# DOAN2.net
KiCad netlist of a schematic drawn in Altium Designer
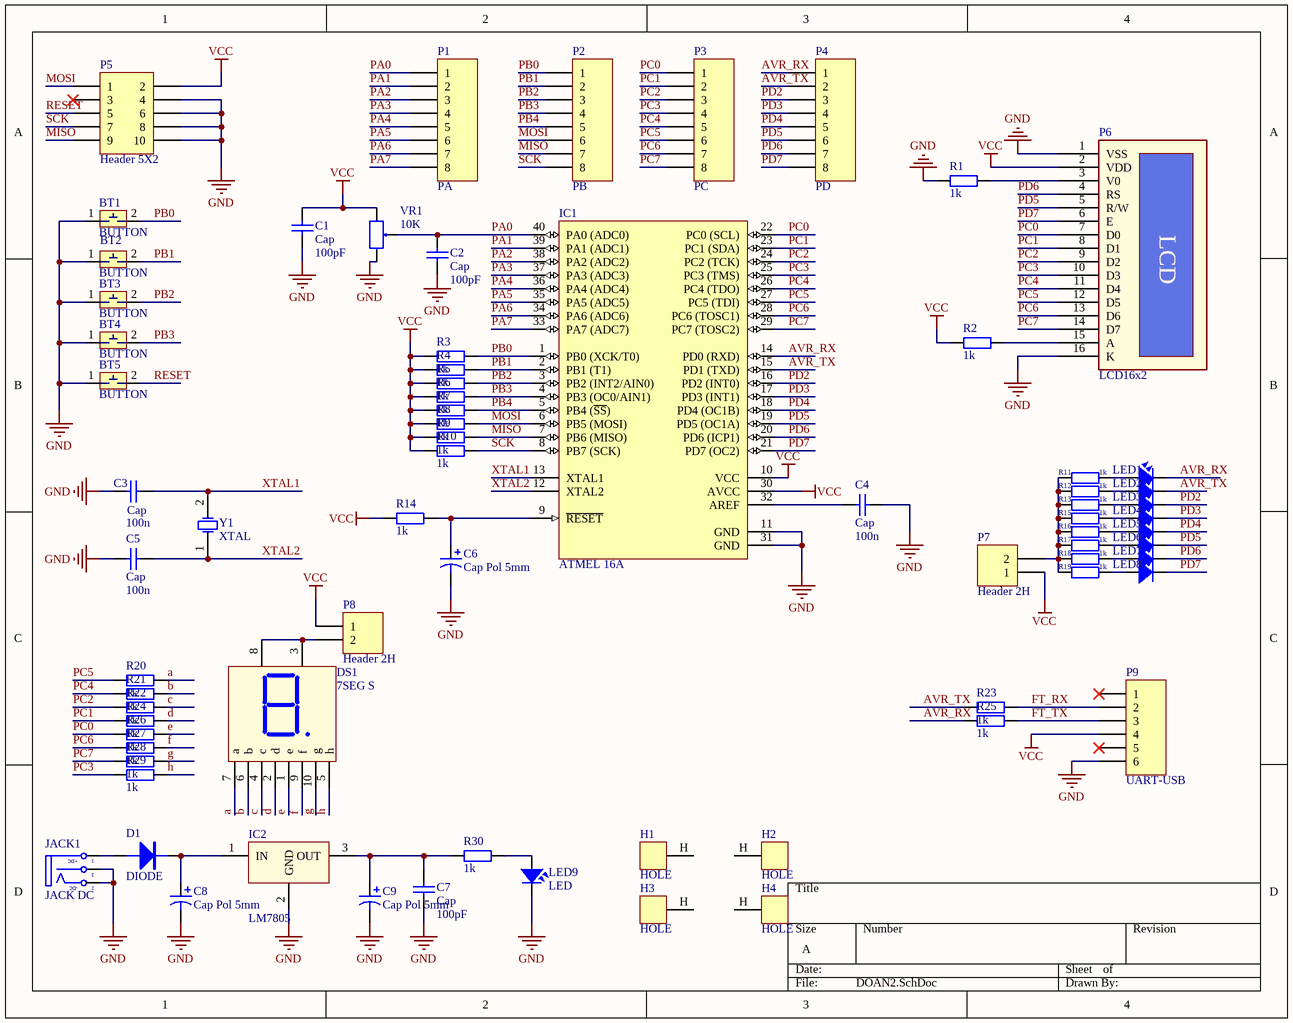
[diagram p0: DOAN2.SchDoc]

(export (version "E")
  (design (tool "Eeschema 10.0.6"))
  (components
    (comp (ref "BT1")
      (value "BUTTON")
      (footprint "BUTTON 4 PIN")
      (libsource (lib "ThinhNguyenLib") (part "BUTTON"))
    )
    (comp (ref "BT2")
      (value "BUTTON")
      (footprint "BUTTON 4 PIN")
      (libsource (lib "ThinhNguyenLib") (part "BUTTON"))
    )
    (comp (ref "BT3")
      (value "BUTTON")
      (footprint "BUTTON 4 PIN")
      (libsource (lib "ThinhNguyenLib") (part "BUTTON"))
    )
    (comp (ref "BT4")
      (value "BUTTON")
      (footprint "BUTTON 4 PIN")
      (libsource (lib "ThinhNguyenLib") (part "BUTTON"))
    )
    (comp (ref "BT5")
      (value "BUTTON")
      (footprint "BUTTON 4 PIN")
      (libsource (lib "ThinhNguyenLib") (part "BUTTON"))
    )
    (comp (ref "C1")
      (value "Cap")
      (footprint "CAP 10x DIP")
      (description "Capacitor")
      (fields (field (name "ALTIUM_VALUE") "100pF") (field (name "PUBLISHER") "Altium Limited"))
      (libsource (lib "Miscellaneous Devices") (part "Cap"))
    )
    (comp (ref "C2")
      (value "Cap")
      (footprint "CAP 10x DIP")
      (description "Capacitor")
      (fields (field (name "ALTIUM_VALUE") "100pF") (field (name "PUBLISHER") "Altium Limited"))
      (libsource (lib "Miscellaneous Devices") (part "Cap"))
    )
    (comp (ref "C3")
      (value "Cap")
      (footprint "CAP 10x DIP")
      (description "Capacitor")
      (fields (field (name "ALTIUM_VALUE") "100n") (field (name "PUBLISHER") "Altium Limited"))
      (libsource (lib "Miscellaneous Devices") (part "Cap"))
    )
    (comp (ref "C4")
      (value "Cap")
      (footprint "CAP 10x DIP")
      (description "Capacitor")
      (fields (field (name "ALTIUM_VALUE") "100n") (field (name "PUBLISHER") "Altium Limited"))
      (libsource (lib "Miscellaneous Devices") (part "Cap"))
    )
    (comp (ref "C5")
      (value "Cap")
      (footprint "CAP 10x DIP")
      (description "Capacitor")
      (fields (field (name "ALTIUM_VALUE") "100n") (field (name "PUBLISHER") "Altium Limited"))
      (libsource (lib "Miscellaneous Devices") (part "Cap"))
    )
    (comp (ref "C6")
      (value "Cap Pol 5mm")
      (footprint "C5mm")
      (description "Polarized Capacitor (Axial)")
      (fields (field (name "PUBLISHER") "Altium Limited"))
      (libsource (lib "My Library") (part "Cap Pol 5mm"))
    )
    (comp (ref "C7")
      (value "Cap")
      (footprint "CAP 10x DIP")
      (description "Capacitor")
      (fields (field (name "ALTIUM_VALUE") "100pF") (field (name "PUBLISHER") "Altium Limited"))
      (libsource (lib "Miscellaneous Devices") (part "Cap"))
    )
    (comp (ref "C8")
      (value "Cap Pol 5mm")
      (footprint "CAP_D10")
      (description "Polarized Capacitor (Axial)")
      (fields (field (name "PUBLISHER") "Altium Limited"))
      (libsource (lib "My Library") (part "Cap Pol 5mm"))
    )
    (comp (ref "C9")
      (value "Cap Pol 5mm")
      (footprint "CAP_D18")
      (description "Polarized Capacitor (Axial)")
      (fields (field (name "PUBLISHER") "Altium Limited"))
      (libsource (lib "My Library") (part "Cap Pol 5mm"))
    )
    (comp (ref "D1")
      (value "DIODE")
      (footprint "DIODE DIP")
      (libsource (lib "ThinhNguyenLib") (part "DIODE"))
    )
    (comp (ref "DS1")
      (value "7SEG S")
      (footprint "7SEGS")
      (description "Single 7 Seg Dipslay")
      (libsource (lib "My Library") (part "LED7S"))
    )
    (comp (ref "H1") (value "HOLE") (footprint "HOLE") (libsource (lib "") (part "HOLE_1")))
    (comp (ref "H2") (value "HOLE") (footprint "HOLE") (libsource (lib "ThinhNguyenLib") (part "HOLE")))
    (comp (ref "H3") (value "HOLE") (footprint "HOLE") (libsource (lib "") (part "HOLE_1")))
    (comp (ref "H4") (value "HOLE") (footprint "HOLE") (libsource (lib "ThinhNguyenLib") (part "HOLE")))
    (comp (ref "IC1")
      (value "ATMEL 16A")
      (footprint "DIP40/W0.6")
      (description "8-Bit AVR Microcontroller with 16K Bytes of In-System Programmable Flash Memory")
      (libsource (lib "My Library") (part "ATmega16A-PU"))
    )
    (comp (ref "IC2")
      (value "LM7805")
      (footprint "QTO-220")
      (description "On ap +, from + 5 to + 24VDC")
      (libsource (lib "My Library") (part "LM78xx"))
    )
    (comp (ref "JACK1")
      (value "JACK DC")
      (footprint "JACK DC")
      (libsource (lib "ThinhNguyenLib") (part "JACK DC"))
    )
    (comp (ref "LED1")
      (value "~")
      (footprint "LED-5 GRe")
      (description "LED Single colour Green and Red")
      (libsource (lib "My Library") (part "LED"))
    )
    (comp (ref "LED2")
      (value "~")
      (footprint "LED-5 GRe")
      (description "LED Single colour Green and Red")
      (libsource (lib "My Library") (part "LED"))
    )
    (comp (ref "LED3")
      (value "~")
      (footprint "LED-5 GRe")
      (description "LED Single colour Green and Red")
      (libsource (lib "My Library") (part "LED"))
    )
    (comp (ref "LED4")
      (value "~")
      (footprint "LED-5 GRe")
      (description "LED Single colour Green and Red")
      (libsource (lib "My Library") (part "LED"))
    )
    (comp (ref "LED5")
      (value "~")
      (footprint "LED-5 GRe")
      (description "LED Single colour Green and Red")
      (libsource (lib "My Library") (part "LED"))
    )
    (comp (ref "LED6")
      (value "~")
      (footprint "LED-5 GRe")
      (description "LED Single colour Green and Red")
      (libsource (lib "My Library") (part "LED"))
    )
    (comp (ref "LED7")
      (value "~")
      (footprint "LED-5 GRe")
      (description "LED Single colour Green and Red")
      (libsource (lib "My Library") (part "LED"))
    )
    (comp (ref "LED8")
      (value "~")
      (footprint "LED-5 GRe")
      (description "LED Single colour Green and Red")
      (libsource (lib "My Library") (part "LED"))
    )
    (comp (ref "LED9")
      (value "LED")
      (footprint "LED-5 GRe")
      (description "LED Single colour Green and Red")
      (libsource (lib "My Library") (part "LED"))
    )
    (comp (ref "P1")
      (value "PA")
      (footprint "HDR1X8")
      (fields (field (name "PUBLISHER") "Altium Limited"))
      (libsource (lib "ThinhNguyenLib") (part "Header 8"))
    )
    (comp (ref "P2")
      (value "PB")
      (footprint "HDR1X8")
      (fields (field (name "PUBLISHER") "Altium Limited"))
      (libsource (lib "ThinhNguyenLib") (part "Header 8"))
    )
    (comp (ref "P3")
      (value "PC")
      (footprint "HDR1X8")
      (fields (field (name "PUBLISHER") "Altium Limited"))
      (libsource (lib "ThinhNguyenLib") (part "Header 8"))
    )
    (comp (ref "P4")
      (value "PD")
      (footprint "HDR1X8")
      (fields (field (name "PUBLISHER") "Altium Limited"))
      (libsource (lib "ThinhNguyenLib") (part "Header 8"))
    )
    (comp (ref "P5")
      (value "Header 5X2")
      (footprint "IDC10 MALE")
      (fields (field (name "PUBLISHER") "Altium Limited"))
      (libsource (lib "ThinhNguyenLib") (part "Header 5X2"))
    )
    (comp (ref "P6") (value "LCD16x2") (footprint "HDR1X16") (libsource (lib "My Library") (part "LCD Text")))
    (comp (ref "P7")
      (value "Header 2H")
      (footprint "HDR1X2")
      (fields (field (name "PUBLISHER") "Altium Limited"))
      (libsource (lib "") (part "Header 2H_1"))
    )
    (comp (ref "P8")
      (value "Header 2H")
      (footprint "HDR1X2")
      (fields (field (name "PUBLISHER") "Altium Limited"))
      (libsource (lib "ThinhNguyenLib") (part "Header 2H"))
    )
    (comp (ref "P9")
      (value "UART-USB")
      (footprint "HDR1X6")
      (fields (field (name "PUBLISHER") "Altium Limited"))
      (libsource (lib "ThinhNguyenLib") (part "Header 6"))
    )
    (comp (ref "R1") (value "1k") (footprint "R1/2W") (libsource (lib "ThinhNguyenLib") (part "RESISTOR")))
    (comp (ref "R2") (value "1k") (footprint "R1/2W") (libsource (lib "ThinhNguyenLib") (part "RESISTOR")))
    (comp (ref "R3") (value "1k") (footprint "R1/2W") (libsource (lib "ThinhNguyenLib") (part "RESISTOR")))
    (comp (ref "R4") (value "1k") (footprint "R1/2W") (libsource (lib "ThinhNguyenLib") (part "RESISTOR")))
    (comp (ref "R5") (value "1k") (footprint "R1/2W") (libsource (lib "ThinhNguyenLib") (part "RESISTOR")))
    (comp (ref "R6") (value "1k") (footprint "R1/2W") (libsource (lib "ThinhNguyenLib") (part "RESISTOR")))
    (comp (ref "R7") (value "1k") (footprint "R1/2W") (libsource (lib "ThinhNguyenLib") (part "RESISTOR")))
    (comp (ref "R8") (value "1k") (footprint "R1/2W") (libsource (lib "ThinhNguyenLib") (part "RESISTOR")))
    (comp (ref "R9") (value "1k") (footprint "R1/2W") (libsource (lib "ThinhNguyenLib") (part "RESISTOR")))
    (comp (ref "R10") (value "1k") (footprint "R1/2W") (libsource (lib "ThinhNguyenLib") (part "RESISTOR")))
    (comp (ref "R11") (value "1k") (footprint "R1/2W") (libsource (lib "ThinhNguyenLib") (part "RESISTOR")))
    (comp (ref "R12") (value "1k") (footprint "R1/2W") (libsource (lib "ThinhNguyenLib") (part "RESISTOR")))
    (comp (ref "R13") (value "1k") (footprint "R1/2W") (libsource (lib "ThinhNguyenLib") (part "RESISTOR")))
    (comp (ref "R14") (value "1k") (footprint "R1/2W") (libsource (lib "ThinhNguyenLib") (part "RESISTOR")))
    (comp (ref "R15") (value "1k") (footprint "R1/2W") (libsource (lib "ThinhNguyenLib") (part "RESISTOR")))
    (comp (ref "R16") (value "1k") (footprint "R1/2W") (libsource (lib "ThinhNguyenLib") (part "RESISTOR")))
    (comp (ref "R17") (value "1k") (footprint "R1/2W") (libsource (lib "ThinhNguyenLib") (part "RESISTOR")))
    (comp (ref "R18") (value "1k") (footprint "R1/2W") (libsource (lib "ThinhNguyenLib") (part "RESISTOR")))
    (comp (ref "R19") (value "1k") (footprint "R1/2W") (libsource (lib "ThinhNguyenLib") (part "RESISTOR")))
    (comp (ref "R20") (value "1k") (footprint "R1/2W") (libsource (lib "ThinhNguyenLib") (part "RESISTOR")))
    (comp (ref "R21") (value "1k") (footprint "R1/2W") (libsource (lib "ThinhNguyenLib") (part "RESISTOR")))
    (comp (ref "R22") (value "1k") (footprint "R1/2W") (libsource (lib "ThinhNguyenLib") (part "RESISTOR")))
    (comp (ref "R23") (value "1k") (footprint "R1/2W") (libsource (lib "ThinhNguyenLib") (part "RESISTOR")))
    (comp (ref "R24") (value "1k") (footprint "R1/2W") (libsource (lib "ThinhNguyenLib") (part "RESISTOR")))
    (comp (ref "R25") (value "1k") (footprint "R1/2W") (libsource (lib "ThinhNguyenLib") (part "RESISTOR")))
    (comp (ref "R26") (value "1k") (footprint "R1/2W") (libsource (lib "ThinhNguyenLib") (part "RESISTOR")))
    (comp (ref "R27") (value "1k") (footprint "R1/2W") (libsource (lib "ThinhNguyenLib") (part "RESISTOR")))
    (comp (ref "R28") (value "1k") (footprint "R1/2W") (libsource (lib "ThinhNguyenLib") (part "RESISTOR")))
    (comp (ref "R29") (value "1k") (footprint "R1/2W") (libsource (lib "ThinhNguyenLib") (part "RESISTOR")))
    (comp (ref "R30") (value "1k") (footprint "R1/2W") (libsource (lib "ThinhNguyenLib") (part "RESISTOR")))
    (comp (ref "VR1") (value "10K") (footprint "RVAR") (libsource (lib "ThinhNguyenLib") (part "VAR RES")))
    (comp (ref "Y1")
      (value "XTAL")
      (footprint "CRYSTAL DIP")
      (description "Crystal Oscillator")
      (fields (field (name "PUBLISHER") "Altium Limited"))
      (libsource (lib "Miscellaneous Devices") (part "XTAL"))
    )
  )
  (nets
    (net (code "1") (name "/AVR_RX") (class "Default")
      (node (ref "IC1") (pin "14") (pinfunction "PD0_(RXD)_14") (pintype "bidirectional"))
      (node (ref "LED1") (pin "2") (pinfunction "2_2") (pintype "passive"))
      (node (ref "P4") (pin "1") (pinfunction "1_1") (pintype "passive"))
      (node (ref "R25") (pin "1") (pinfunction "1_1") (pintype "passive"))
    )
    (net (code "2") (name "/AVR_TX") (class "Default")
      (node (ref "IC1") (pin "15") (pinfunction "PD1_(TXD)_15") (pintype "bidirectional"))
      (node (ref "LED2") (pin "2") (pinfunction "2_2") (pintype "passive"))
      (node (ref "P4") (pin "2") (pinfunction "2_2") (pintype "passive"))
      (node (ref "R23") (pin "1") (pinfunction "1_1") (pintype "passive"))
    )
    (net (code "3") (name "/FT_RX") (class "Default")
      (node (ref "P9") (pin "2") (pinfunction "2_2") (pintype "passive"))
      (node (ref "R23") (pin "2") (pinfunction "2_2") (pintype "passive"))
    )
    (net (code "4") (name "/FT_TX") (class "Default")
      (node (ref "P9") (pin "3") (pinfunction "3_3") (pintype "passive"))
      (node (ref "R25") (pin "2") (pinfunction "2_2") (pintype "passive"))
    )
    (net (code "5") (name "/MISO") (class "Default")
      (node (ref "IC1") (pin "7") (pinfunction "PB6_(MISO)_7") (pintype "bidirectional"))
      (node (ref "P2") (pin "7") (pinfunction "7_7") (pintype "passive"))
      (node (ref "P5") (pin "9") (pinfunction "9_9") (pintype "passive"))
      (node (ref "R9") (pin "2") (pinfunction "2_2") (pintype "passive"))
    )
    (net (code "6") (name "/MOSI") (class "Default")
      (node (ref "IC1") (pin "6") (pinfunction "PB5_(MOSI)_6") (pintype "bidirectional"))
      (node (ref "P2") (pin "6") (pinfunction "6_6") (pintype "passive"))
      (node (ref "P5") (pin "1") (pinfunction "1_1") (pintype "passive"))
      (node (ref "R8") (pin "2") (pinfunction "2_2") (pintype "passive"))
    )
    (net (code "7") (name "/PA0") (class "Default")
      (node (ref "C2") (pin "2") (pinfunction "2_2") (pintype "passive"))
      (node (ref "IC1") (pin "40") (pinfunction "PA0_(ADC0)_40") (pintype "bidirectional"))
      (node (ref "P1") (pin "1") (pinfunction "1_1") (pintype "passive"))
      (node (ref "VR1") (pin "2") (pinfunction "2_2") (pintype "passive"))
    )
    (net (code "8") (name "/PA1") (class "Default")
      (node (ref "IC1") (pin "39") (pinfunction "PA1_(ADC1)_39") (pintype "bidirectional"))
      (node (ref "P1") (pin "2") (pinfunction "2_2") (pintype "passive"))
    )
    (net (code "9") (name "/PA2") (class "Default")
      (node (ref "IC1") (pin "38") (pinfunction "PA2_(ADC2)_38") (pintype "bidirectional"))
      (node (ref "P1") (pin "3") (pinfunction "3_3") (pintype "passive"))
    )
    (net (code "10") (name "/PA3") (class "Default")
      (node (ref "IC1") (pin "37") (pinfunction "PA3_(ADC3)_37") (pintype "bidirectional"))
      (node (ref "P1") (pin "4") (pinfunction "4_4") (pintype "passive"))
    )
    (net (code "11") (name "/PA4") (class "Default")
      (node (ref "IC1") (pin "36") (pinfunction "PA4_(ADC4)_36") (pintype "bidirectional"))
      (node (ref "P1") (pin "5") (pinfunction "5_5") (pintype "passive"))
    )
    (net (code "12") (name "/PA5") (class "Default")
      (node (ref "IC1") (pin "35") (pinfunction "PA5_(ADC5)_35") (pintype "bidirectional"))
      (node (ref "P1") (pin "6") (pinfunction "6_6") (pintype "passive"))
    )
    (net (code "13") (name "/PA6") (class "Default")
      (node (ref "IC1") (pin "34") (pinfunction "PA6_(ADC6)_34") (pintype "bidirectional"))
      (node (ref "P1") (pin "7") (pinfunction "7_7") (pintype "passive"))
    )
    (net (code "14") (name "/PA7") (class "Default")
      (node (ref "IC1") (pin "33") (pinfunction "PA7_(ADC7)_33") (pintype "bidirectional"))
      (node (ref "P1") (pin "8") (pinfunction "8_8") (pintype "passive"))
    )
    (net (code "15") (name "/PB0") (class "Default")
      (node (ref "BT1") (pin "2") (pinfunction "2_2") (pintype "passive"))
      (node (ref "IC1") (pin "1") (pinfunction "PB0_(XCK/T0)_1") (pintype "bidirectional"))
      (node (ref "P2") (pin "1") (pinfunction "1_1") (pintype "passive"))
      (node (ref "R3") (pin "2") (pinfunction "2_2") (pintype "passive"))
    )
    (net (code "16") (name "/PB1") (class "Default")
      (node (ref "BT2") (pin "2") (pinfunction "2_2") (pintype "passive"))
      (node (ref "IC1") (pin "2") (pinfunction "PB1_(T1)_2") (pintype "bidirectional"))
      (node (ref "P2") (pin "2") (pinfunction "2_2") (pintype "passive"))
      (node (ref "R4") (pin "2") (pinfunction "2_2") (pintype "passive"))
    )
    (net (code "17") (name "/PB2") (class "Default")
      (node (ref "BT3") (pin "2") (pinfunction "2_2") (pintype "passive"))
      (node (ref "IC1") (pin "3") (pinfunction "PB2_(INT2/AIN0)_3") (pintype "bidirectional"))
      (node (ref "P2") (pin "3") (pinfunction "3_3") (pintype "passive"))
      (node (ref "R5") (pin "2") (pinfunction "2_2") (pintype "passive"))
    )
    (net (code "18") (name "/PB3") (class "Default")
      (node (ref "BT4") (pin "2") (pinfunction "2_2") (pintype "passive"))
      (node (ref "IC1") (pin "4") (pinfunction "PB3_(OC0/AIN1)_4") (pintype "bidirectional"))
      (node (ref "P2") (pin "4") (pinfunction "4_4") (pintype "passive"))
      (node (ref "R6") (pin "2") (pinfunction "2_2") (pintype "passive"))
    )
    (net (code "19") (name "/PB4") (class "Default")
      (node (ref "IC1") (pin "5") (pinfunction "PB4_(~{SS})_5") (pintype "bidirectional"))
      (node (ref "P2") (pin "5") (pinfunction "5_5") (pintype "passive"))
      (node (ref "R7") (pin "2") (pinfunction "2_2") (pintype "passive"))
    )
    (net (code "20") (name "/PC0") (class "Default")
      (node (ref "IC1") (pin "22") (pinfunction "PC0_(SCL)_22") (pintype "bidirectional"))
      (node (ref "P3") (pin "1") (pinfunction "1_1") (pintype "passive"))
      (node (ref "P6") (pin "7") (pinfunction "D0_7") (pintype "passive"))
      (node (ref "R26") (pin "1") (pinfunction "1_1") (pintype "passive"))
    )
    (net (code "21") (name "/PC1") (class "Default")
      (node (ref "IC1") (pin "23") (pinfunction "PC1_(SDA)_23") (pintype "bidirectional"))
      (node (ref "P3") (pin "2") (pinfunction "2_2") (pintype "passive"))
      (node (ref "P6") (pin "8") (pinfunction "D1_8") (pintype "passive"))
      (node (ref "R24") (pin "1") (pinfunction "1_1") (pintype "passive"))
    )
    (net (code "22") (name "/PC2") (class "Default")
      (node (ref "IC1") (pin "24") (pinfunction "PC2_(TCK)_24") (pintype "bidirectional"))
      (node (ref "P3") (pin "3") (pinfunction "3_3") (pintype "passive"))
      (node (ref "P6") (pin "9") (pinfunction "D2_9") (pintype "passive"))
      (node (ref "R22") (pin "1") (pinfunction "1_1") (pintype "passive"))
    )
    (net (code "23") (name "/PC3") (class "Default")
      (node (ref "IC1") (pin "25") (pinfunction "PC3_(TMS)_25") (pintype "bidirectional"))
      (node (ref "P3") (pin "4") (pinfunction "4_4") (pintype "passive"))
      (node (ref "P6") (pin "10") (pinfunction "D3_10") (pintype "passive"))
      (node (ref "R29") (pin "1") (pinfunction "1_1") (pintype "passive"))
    )
    (net (code "24") (name "/PC4") (class "Default")
      (node (ref "IC1") (pin "26") (pinfunction "PC4_(TDO)_26") (pintype "bidirectional"))
      (node (ref "P3") (pin "5") (pinfunction "5_5") (pintype "passive"))
      (node (ref "P6") (pin "11") (pinfunction "D4_11") (pintype "passive"))
      (node (ref "R21") (pin "1") (pinfunction "1_1") (pintype "passive"))
    )
    (net (code "25") (name "/PC5") (class "Default")
      (node (ref "IC1") (pin "27") (pinfunction "PC5_(TDI)_27") (pintype "bidirectional"))
      (node (ref "P3") (pin "6") (pinfunction "6_6") (pintype "passive"))
      (node (ref "P6") (pin "12") (pinfunction "D5_12") (pintype "passive"))
      (node (ref "R20") (pin "1") (pinfunction "1_1") (pintype "passive"))
    )
    (net (code "26") (name "/PC6") (class "Default")
      (node (ref "IC1") (pin "28") (pinfunction "PC6_(TOSC1)_28") (pintype "bidirectional"))
      (node (ref "P3") (pin "7") (pinfunction "7_7") (pintype "passive"))
      (node (ref "P6") (pin "13") (pinfunction "D6_13") (pintype "passive"))
      (node (ref "R27") (pin "1") (pinfunction "1_1") (pintype "passive"))
    )
    (net (code "27") (name "/PC7") (class "Default")
      (node (ref "IC1") (pin "29") (pinfunction "PC7_(TOSC2)_29") (pintype "bidirectional"))
      (node (ref "P3") (pin "8") (pinfunction "8_8") (pintype "passive"))
      (node (ref "P6") (pin "14") (pinfunction "D7_14") (pintype "passive"))
      (node (ref "R28") (pin "1") (pinfunction "1_1") (pintype "passive"))
    )
    (net (code "28") (name "/PD2") (class "Default")
      (node (ref "IC1") (pin "16") (pinfunction "PD2_(INT0)_16") (pintype "bidirectional"))
      (node (ref "LED3") (pin "2") (pinfunction "2_2") (pintype "passive"))
      (node (ref "P4") (pin "3") (pinfunction "3_3") (pintype "passive"))
    )
    (net (code "29") (name "/PD3") (class "Default")
      (node (ref "IC1") (pin "17") (pinfunction "PD3_(INT1)_17") (pintype "bidirectional"))
      (node (ref "LED4") (pin "2") (pinfunction "2_2") (pintype "passive"))
      (node (ref "P4") (pin "4") (pinfunction "4_4") (pintype "passive"))
    )
    (net (code "30") (name "/PD4") (class "Default")
      (node (ref "IC1") (pin "18") (pinfunction "PD4_(OC1B)_18") (pintype "bidirectional"))
      (node (ref "LED5") (pin "2") (pinfunction "2_2") (pintype "passive"))
      (node (ref "P4") (pin "5") (pinfunction "5_5") (pintype "passive"))
    )
    (net (code "31") (name "/PD5") (class "Default")
      (node (ref "IC1") (pin "19") (pinfunction "PD5_(OC1A)_19") (pintype "bidirectional"))
      (node (ref "LED6") (pin "2") (pinfunction "2_2") (pintype "passive"))
      (node (ref "P4") (pin "6") (pinfunction "6_6") (pintype "passive"))
      (node (ref "P6") (pin "5") (pinfunction "R/W_5") (pintype "passive"))
    )
    (net (code "32") (name "/PD6") (class "Default")
      (node (ref "IC1") (pin "20") (pinfunction "PD6_(ICP1)_20") (pintype "bidirectional"))
      (node (ref "LED7") (pin "2") (pinfunction "2_2") (pintype "passive"))
      (node (ref "P4") (pin "7") (pinfunction "7_7") (pintype "passive"))
      (node (ref "P6") (pin "4") (pinfunction "RS_4") (pintype "passive"))
    )
    (net (code "33") (name "/PD7") (class "Default")
      (node (ref "IC1") (pin "21") (pinfunction "PD7_(OC2)_21") (pintype "bidirectional"))
      (node (ref "LED8") (pin "2") (pinfunction "2_2") (pintype "passive"))
      (node (ref "P4") (pin "8") (pinfunction "8_8") (pintype "passive"))
      (node (ref "P6") (pin "6") (pinfunction "E_6") (pintype "passive"))
    )
    (net (code "34") (name "/RESET") (class "Default")
      (node (ref "BT5") (pin "2") (pinfunction "2_2") (pintype "passive"))
      (node (ref "P5") (pin "5") (pinfunction "5_5") (pintype "passive"))
    )
    (net (code "35") (name "/SCK") (class "Default")
      (node (ref "IC1") (pin "8") (pinfunction "PB7_(SCK)_8") (pintype "bidirectional"))
      (node (ref "P2") (pin "8") (pinfunction "8_8") (pintype "passive"))
      (node (ref "P5") (pin "7") (pinfunction "7_7") (pintype "passive"))
      (node (ref "R10") (pin "2") (pinfunction "2_2") (pintype "passive"))
    )
    (net (code "36") (name "/XTAL1") (class "Default")
      (node (ref "C3") (pin "2") (pinfunction "2_2") (pintype "passive"))
      (node (ref "IC1") (pin "13") (pinfunction "XTAL1_13") (pintype "passive"))
      (node (ref "Y1") (pin "2") (pinfunction "OSC2_2") (pintype "passive"))
    )
    (net (code "37") (name "/XTAL2") (class "Default")
      (node (ref "C5") (pin "2") (pinfunction "2_2") (pintype "passive"))
      (node (ref "IC1") (pin "12") (pinfunction "XTAL2_12") (pintype "passive"))
      (node (ref "Y1") (pin "1") (pinfunction "OSC1_1") (pintype "passive"))
    )
    (net (code "38") (name "/a") (class "Default")
      (node (ref "DS1") (pin "7") (pinfunction "a_7") (pintype "passive"))
      (node (ref "R20") (pin "2") (pinfunction "2_2") (pintype "passive"))
    )
    (net (code "39") (name "/b") (class "Default")
      (node (ref "DS1") (pin "6") (pinfunction "b_6") (pintype "passive"))
      (node (ref "R21") (pin "2") (pinfunction "2_2") (pintype "passive"))
    )
    (net (code "40") (name "/c") (class "Default")
      (node (ref "DS1") (pin "4") (pinfunction "c_4") (pintype "passive"))
      (node (ref "R22") (pin "2") (pinfunction "2_2") (pintype "passive"))
    )
    (net (code "41") (name "/d") (class "Default")
      (node (ref "DS1") (pin "2") (pinfunction "d_2") (pintype "passive"))
      (node (ref "R24") (pin "2") (pinfunction "2_2") (pintype "passive"))
    )
    (net (code "42") (name "/e") (class "Default")
      (node (ref "DS1") (pin "1") (pinfunction "e_1") (pintype "passive"))
      (node (ref "R26") (pin "2") (pinfunction "2_2") (pintype "passive"))
    )
    (net (code "43") (name "/f") (class "Default")
      (node (ref "DS1") (pin "9") (pinfunction "f_9") (pintype "passive"))
      (node (ref "R27") (pin "2") (pinfunction "2_2") (pintype "passive"))
    )
    (net (code "44") (name "/g") (class "Default")
      (node (ref "DS1") (pin "10") (pinfunction "g_10") (pintype "passive"))
      (node (ref "R28") (pin "2") (pinfunction "2_2") (pintype "passive"))
    )
    (net (code "45") (name "/h") (class "Default")
      (node (ref "DS1") (pin "5") (pinfunction "h_5") (pintype "passive"))
      (node (ref "R29") (pin "2") (pinfunction "2_2") (pintype "passive"))
    )
    (net (code "46") (name "GND") (class "Default")
      (node (ref "BT1") (pin "1") (pinfunction "1_1") (pintype "passive"))
      (node (ref "BT2") (pin "1") (pinfunction "1_1") (pintype "passive"))
      (node (ref "BT3") (pin "1") (pinfunction "1_1") (pintype "passive"))
      (node (ref "BT4") (pin "1") (pinfunction "1_1") (pintype "passive"))
      (node (ref "BT5") (pin "1") (pinfunction "1_1") (pintype "passive"))
      (node (ref "C1") (pin "1") (pinfunction "1_1") (pintype "passive"))
      (node (ref "C2") (pin "1") (pinfunction "1_1") (pintype "passive"))
      (node (ref "C3") (pin "1") (pinfunction "1_1") (pintype "passive"))
      (node (ref "C4") (pin "2") (pinfunction "2_2") (pintype "passive"))
      (node (ref "C5") (pin "1") (pinfunction "1_1") (pintype "passive"))
      (node (ref "C6") (pin "2") (pinfunction "2_2") (pintype "passive"))
      (node (ref "C7") (pin "1") (pinfunction "1_1") (pintype "passive"))
      (node (ref "C8") (pin "2") (pinfunction "2_2") (pintype "passive"))
      (node (ref "C9") (pin "2") (pinfunction "2_2") (pintype "passive"))
      (node (ref "IC1") (pin "11") (pinfunction "GND_11") (pintype "power_in"))
      (node (ref "IC1") (pin "31") (pinfunction "GND_31") (pintype "power_in"))
      (node (ref "IC2") (pin "2") (pinfunction "GND_2") (pintype "passive"))
      (node (ref "JACK1") (pin "2") (pinfunction "TN_2") (pintype "passive"))
      (node (ref "JACK1") (pin "3") (pinfunction "S_3") (pintype "power_in"))
      (node (ref "LED9") (pin "2") (pinfunction "2_2") (pintype "passive"))
      (node (ref "P5") (pin "10") (pinfunction "10_10") (pintype "passive"))
      (node (ref "P5") (pin "4") (pinfunction "4_4") (pintype "passive"))
      (node (ref "P5") (pin "6") (pinfunction "6_6") (pintype "passive"))
      (node (ref "P5") (pin "8") (pinfunction "8_8") (pintype "passive"))
      (node (ref "P6") (pin "1") (pinfunction "VSS_1") (pintype "passive"))
      (node (ref "P6") (pin "16") (pinfunction "K_16") (pintype "passive"))
      (node (ref "P9") (pin "6") (pinfunction "6_6") (pintype "passive"))
      (node (ref "R1") (pin "2") (pinfunction "2_2") (pintype "passive"))
      (node (ref "VR1") (pin "3") (pinfunction "3_3") (pintype "passive"))
    )
    (net (code "47") (name "Net-(DS1-Vcc-Pad3)") (class "Default")
      (node (ref "DS1") (pin "3") (pinfunction "Vcc_3") (pintype "passive"))
      (node (ref "DS1") (pin "8") (pinfunction "Vcc_8") (pintype "passive"))
      (node (ref "P8") (pin "2") (pinfunction "2_2") (pintype "passive"))
    )
    (net (code "48") (name "Net-(IC1-AREF)") (class "Default")
      (node (ref "C4") (pin "1") (pinfunction "1_1") (pintype "passive"))
      (node (ref "IC1") (pin "32") (pinfunction "AREF_32") (pintype "power_in"))
    )
    (net (code "49") (name "Net-(IC1-~{RESET})") (class "Default")
      (node (ref "C6") (pin "1") (pinfunction "1_1") (pintype "passive"))
      (node (ref "IC1") (pin "9") (pinfunction "~{RESET}_9") (pintype "input"))
      (node (ref "R14") (pin "1") (pinfunction "1_1") (pintype "passive"))
    )
    (net (code "50") (name "Net-(IC2-IN)") (class "Default")
      (node (ref "C8") (pin "1") (pinfunction "1_1") (pintype "passive"))
      (node (ref "D1") (pin "2") (pinfunction "2_2") (pintype "passive"))
      (node (ref "IC2") (pin "1") (pinfunction "IN_1") (pintype "passive"))
    )
    (net (code "51") (name "Net-(IC2-OUT)") (class "Default")
      (node (ref "C7") (pin "2") (pinfunction "2_2") (pintype "passive"))
      (node (ref "C9") (pin "1") (pinfunction "1_1") (pintype "passive"))
      (node (ref "IC2") (pin "3") (pinfunction "OUT_3") (pintype "passive"))
      (node (ref "R30") (pin "1") (pinfunction "1_1") (pintype "passive"))
    )
    (net (code "52") (name "Net-(JACK1-T)") (class "Default")
      (node (ref "D1") (pin "1") (pinfunction "1_1") (pintype "passive"))
      (node (ref "JACK1") (pin "1") (pinfunction "T_1") (pintype "passive"))
    )
    (net (code "53") (name "Net-(LED1-Pad1)") (class "Default")
      (node (ref "LED1") (pin "1") (pinfunction "1_1") (pintype "passive"))
      (node (ref "R11") (pin "2") (pinfunction "2_2") (pintype "passive"))
    )
    (net (code "54") (name "Net-(LED2-Pad1)") (class "Default")
      (node (ref "LED2") (pin "1") (pinfunction "1_1") (pintype "passive"))
      (node (ref "R12") (pin "2") (pinfunction "2_2") (pintype "passive"))
    )
    (net (code "55") (name "Net-(LED3-Pad1)") (class "Default")
      (node (ref "LED3") (pin "1") (pinfunction "1_1") (pintype "passive"))
      (node (ref "R13") (pin "2") (pinfunction "2_2") (pintype "passive"))
    )
    (net (code "56") (name "Net-(LED4-Pad1)") (class "Default")
      (node (ref "LED4") (pin "1") (pinfunction "1_1") (pintype "passive"))
      (node (ref "R15") (pin "2") (pinfunction "2_2") (pintype "passive"))
    )
    (net (code "57") (name "Net-(LED5-Pad1)") (class "Default")
      (node (ref "LED5") (pin "1") (pinfunction "1_1") (pintype "passive"))
      (node (ref "R16") (pin "2") (pinfunction "2_2") (pintype "passive"))
    )
    (net (code "58") (name "Net-(LED6-Pad1)") (class "Default")
      (node (ref "LED6") (pin "1") (pinfunction "1_1") (pintype "passive"))
      (node (ref "R17") (pin "2") (pinfunction "2_2") (pintype "passive"))
    )
    (net (code "59") (name "Net-(LED7-Pad1)") (class "Default")
      (node (ref "LED7") (pin "1") (pinfunction "1_1") (pintype "passive"))
      (node (ref "R18") (pin "2") (pinfunction "2_2") (pintype "passive"))
    )
    (net (code "60") (name "Net-(LED8-Pad1)") (class "Default")
      (node (ref "LED8") (pin "1") (pinfunction "1_1") (pintype "passive"))
      (node (ref "R19") (pin "2") (pinfunction "2_2") (pintype "passive"))
    )
    (net (code "61") (name "Net-(LED9-Pad1)") (class "Default")
      (node (ref "LED9") (pin "1") (pinfunction "1_1") (pintype "passive"))
      (node (ref "R30") (pin "2") (pinfunction "2_2") (pintype "passive"))
    )
    (net (code "62") (name "Net-(P6-A)") (class "Default")
      (node (ref "P6") (pin "15") (pinfunction "A_15") (pintype "passive"))
      (node (ref "R2") (pin "1") (pinfunction "1_1") (pintype "passive"))
    )
    (net (code "63") (name "Net-(P6-V0)") (class "Default")
      (node (ref "P6") (pin "3") (pinfunction "V0_3") (pintype "passive"))
      (node (ref "R1") (pin "1") (pinfunction "1_1") (pintype "passive"))
    )
    (net (code "64") (name "Net-(P7-Pad2)") (class "Default")
      (node (ref "P7") (pin "2") (pinfunction "2_2") (pintype "passive"))
      (node (ref "R11") (pin "1") (pinfunction "1_1") (pintype "passive"))
      (node (ref "R12") (pin "1") (pinfunction "1_1") (pintype "passive"))
      (node (ref "R13") (pin "1") (pinfunction "1_1") (pintype "passive"))
      (node (ref "R15") (pin "1") (pinfunction "1_1") (pintype "passive"))
      (node (ref "R16") (pin "1") (pinfunction "1_1") (pintype "passive"))
      (node (ref "R17") (pin "1") (pinfunction "1_1") (pintype "passive"))
      (node (ref "R18") (pin "1") (pinfunction "1_1") (pintype "passive"))
      (node (ref "R19") (pin "1") (pinfunction "1_1") (pintype "passive"))
    )
    (net (code "65") (name "VCC") (class "Default")
      (node (ref "C1") (pin "2") (pinfunction "2_2") (pintype "passive"))
      (node (ref "IC1") (pin "10") (pinfunction "VCC_10") (pintype "power_in"))
      (node (ref "IC1") (pin "30") (pinfunction "AVCC_30") (pintype "power_in"))
      (node (ref "P5") (pin "2") (pinfunction "2_2") (pintype "passive"))
      (node (ref "P6") (pin "2") (pinfunction "VDD_2") (pintype "passive"))
      (node (ref "P7") (pin "1") (pinfunction "1_1") (pintype "passive"))
      (node (ref "P8") (pin "1") (pinfunction "1_1") (pintype "passive"))
      (node (ref "P9") (pin "4") (pinfunction "4_4") (pintype "passive"))
      (node (ref "R10") (pin "1") (pinfunction "1_1") (pintype "passive"))
      (node (ref "R14") (pin "2") (pinfunction "2_2") (pintype "passive"))
      (node (ref "R2") (pin "2") (pinfunction "2_2") (pintype "passive"))
      (node (ref "R3") (pin "1") (pinfunction "1_1") (pintype "passive"))
      (node (ref "R4") (pin "1") (pinfunction "1_1") (pintype "passive"))
      (node (ref "R5") (pin "1") (pinfunction "1_1") (pintype "passive"))
      (node (ref "R6") (pin "1") (pinfunction "1_1") (pintype "passive"))
      (node (ref "R7") (pin "1") (pinfunction "1_1") (pintype "passive"))
      (node (ref "R8") (pin "1") (pinfunction "1_1") (pintype "passive"))
      (node (ref "R9") (pin "1") (pinfunction "1_1") (pintype "passive"))
      (node (ref "VR1") (pin "1") (pinfunction "1_1") (pintype "passive"))
    )
    (net (code "66") (name "unconnected-(H1-HOLE-PadH)") (class "Default")
      (node (ref "H1") (pin "H") (pinfunction "HOLE_H") (pintype "passive"))
    )
    (net (code "67") (name "unconnected-(H2-HOLE-PadH)") (class "Default")
      (node (ref "H2") (pin "H") (pinfunction "HOLE_H") (pintype "passive"))
    )
    (net (code "68") (name "unconnected-(H3-HOLE-PadH)") (class "Default")
      (node (ref "H3") (pin "H") (pinfunction "HOLE_H") (pintype "passive"))
    )
    (net (code "69") (name "unconnected-(H4-HOLE-PadH)") (class "Default")
      (node (ref "H4") (pin "H") (pinfunction "HOLE_H") (pintype "passive"))
    )
    (net (code "70") (name "unconnected-(P5-Pad3)") (class "Default")
      (node (ref "P5") (pin "3") (pinfunction "3_3") (pintype "passive+no_connect"))
    )
    (net (code "71") (name "unconnected-(P9-Pad1)") (class "Default")
      (node (ref "P9") (pin "1") (pinfunction "1_1") (pintype "passive+no_connect"))
    )
    (net (code "72") (name "unconnected-(P9-Pad5)") (class "Default")
      (node (ref "P9") (pin "5") (pinfunction "5_5") (pintype "passive+no_connect"))
    )
  )
)
